# lightbar_control.net
KiCad netlist of a schematic drawn in EAGLE
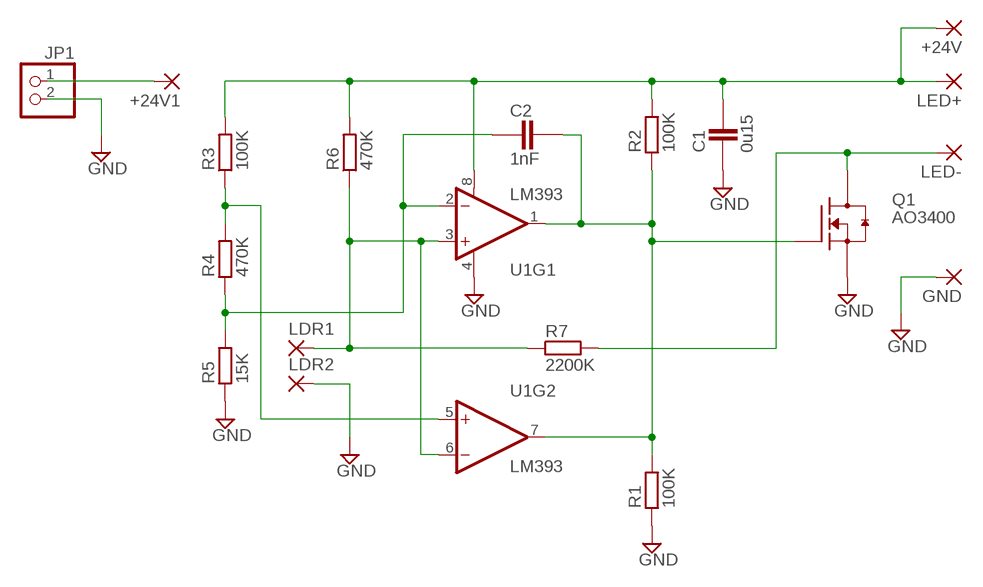
[diagram p0: schematic, sheet 1]

(export (version "E")
  (design (tool "Eeschema 10.0.6"))
  (components
    (comp (ref "+24V")
      (value "SMD2")
      (footprint "eagle-import:SMD1,27-2,54")
      (libsource (lib "eagle-import") (part "SMD2"))
    )
    (comp (ref "+24V1")
      (value "SMD2")
      (footprint "eagle-import:SMD1,27-2,54")
      (libsource (lib "eagle-import") (part "SMD2"))
    )
    (comp (ref "C1")
      (value "0u15")
      (footprint "eagle-import:CAPC2012X145AN")
      (libsource (lib "eagle-import") (part "CAPACITOR_0805"))
    )
    (comp (ref "C2")
      (value "1nF")
      (footprint "eagle-import:CAPC1608X92N")
      (libsource (lib "eagle-import") (part "CAPACITOR_0603"))
    )
    (comp (ref "GND")
      (value "SMD2")
      (footprint "eagle-import:SMD1,27-2,54")
      (libsource (lib "eagle-import") (part "SMD2"))
    )
    (comp (ref "JP1")
      (value "PINHD-1X2/90")
      (footprint "eagle-import:1X02_90")
      (libsource (lib "eagle-import") (part "PINHD-1X2/90"))
    )
    (comp (ref "LDR1")
      (value "SMD2")
      (footprint "eagle-import:SMD1,27-2,54")
      (libsource (lib "eagle-import") (part "SMD2"))
    )
    (comp (ref "LDR2")
      (value "SMD2")
      (footprint "eagle-import:SMD1,27-2,54")
      (libsource (lib "eagle-import") (part "SMD2"))
    )
    (comp (ref "LED+")
      (value "SMD2")
      (footprint "eagle-import:SMD1,27-2,54")
      (libsource (lib "eagle-import") (part "SMD2"))
    )
    (comp (ref "LED-")
      (value "SMD2")
      (footprint "eagle-import:SMD1,27-2,54")
      (libsource (lib "eagle-import") (part "SMD2"))
    )
    (comp (ref "Q1")
      (value "AO3400")
      (footprint "eagle-import:SOT95P280X135-3N")
      (libsource (lib "eagle-import") (part "MOSFET-NCH_SOT-23"))
    )
    (comp (ref "R1")
      (value "100K")
      (footprint "eagle-import:RESC1608X55N")
      (libsource (lib "eagle-import") (part "RESISTOR_0603"))
    )
    (comp (ref "R2")
      (value "100K")
      (footprint "eagle-import:RESC1608X55N")
      (libsource (lib "eagle-import") (part "RESISTOR_0603"))
    )
    (comp (ref "R3")
      (value "100K")
      (footprint "eagle-import:RESC1608X55N")
      (libsource (lib "eagle-import") (part "RESISTOR_0603"))
    )
    (comp (ref "R4")
      (value "470K")
      (footprint "eagle-import:RESC1608X55N")
      (libsource (lib "eagle-import") (part "RESISTOR_0603"))
    )
    (comp (ref "R5")
      (value "15K")
      (footprint "eagle-import:RESC1608X55N")
      (libsource (lib "eagle-import") (part "RESISTOR_0603"))
    )
    (comp (ref "R6")
      (value "470K")
      (footprint "eagle-import:RESC1608X55N")
      (libsource (lib "eagle-import") (part "RESISTOR_0603"))
    )
    (comp (ref "R7")
      (value "2200K")
      (footprint "eagle-import:RESC2012X70N")
      (libsource (lib "eagle-import") (part "RESISTOR_0805"))
    )
    (comp (ref "U1")
      (value "LM393")
      (footprint "eagle-import:SO08")
      (libsource (lib "eagle-import") (part "LM393"))
    )
  )
  (nets
    (net (code "1") (name "GND") (class "Default")
      (node (ref "C1") (pin "1") (pinfunction "1_1") (pintype "passive"))
      (node (ref "GND") (pin "1") (pinfunction "P_1") (pintype "passive"))
      (node (ref "JP1") (pin "2") (pinfunction "2_2") (pintype "passive"))
      (node (ref "LDR2") (pin "1") (pinfunction "P_1") (pintype "passive"))
      (node (ref "Q1") (pin "2") (pinfunction "S_2") (pintype "passive"))
      (node (ref "R1") (pin "1") (pinfunction "1_1") (pintype "passive"))
      (node (ref "R5") (pin "1") (pinfunction "1_1") (pintype "passive"))
      (node (ref "U1") (pin "4") (pinfunction "V-_4") (pintype "power_in"))
    )
    (net (code "2") (name "Net-(+24V-P)") (class "Default")
      (node (ref "+24V") (pin "1") (pinfunction "P_1") (pintype "passive"))
      (node (ref "C1") (pin "2") (pinfunction "2_2") (pintype "passive"))
      (node (ref "LED+") (pin "1") (pinfunction "P_1") (pintype "passive"))
      (node (ref "R2") (pin "2") (pinfunction "2_2") (pintype "passive"))
      (node (ref "R3") (pin "2") (pinfunction "2_2") (pintype "passive"))
      (node (ref "R6") (pin "2") (pinfunction "2_2") (pintype "passive"))
      (node (ref "U1") (pin "8") (pinfunction "V+_8") (pintype "power_in"))
    )
    (net (code "3") (name "Net-(+24V1-P)") (class "Default")
      (node (ref "+24V1") (pin "1") (pinfunction "P_1") (pintype "passive"))
      (node (ref "JP1") (pin "1") (pinfunction "1_1") (pintype "passive"))
    )
    (net (code "4") (name "Net-(LDR1-P)") (class "Default")
      (node (ref "LDR1") (pin "1") (pinfunction "P_1") (pintype "passive"))
      (node (ref "R6") (pin "1") (pinfunction "1_1") (pintype "passive"))
      (node (ref "R7") (pin "1") (pinfunction "1_1") (pintype "passive"))
      (node (ref "U1") (pin "3") (pinfunction "+IN_3") (pintype "input"))
      (node (ref "U1") (pin "6") (pinfunction "-IN_6") (pintype "input"))
    )
    (net (code "5") (name "Net-(LED--P)") (class "Default")
      (node (ref "LED-") (pin "1") (pinfunction "P_1") (pintype "passive"))
      (node (ref "Q1") (pin "3") (pinfunction "D_3") (pintype "passive"))
      (node (ref "R7") (pin "2") (pinfunction "2_2") (pintype "passive"))
    )
    (net (code "6") (name "Net-(Q1-G)") (class "Default")
      (node (ref "C2") (pin "2") (pinfunction "2_2") (pintype "passive"))
      (node (ref "Q1") (pin "1") (pinfunction "G_1") (pintype "passive"))
      (node (ref "R1") (pin "2") (pinfunction "2_2") (pintype "passive"))
      (node (ref "R2") (pin "1") (pinfunction "1_1") (pintype "passive"))
      (node (ref "U1") (pin "1") (pinfunction "OUT_1") (pintype "output"))
      (node (ref "U1") (pin "7") (pinfunction "OUT_7") (pintype "output"))
    )
    (net (code "7") (name "Net-(U1A--IN)") (class "Default")
      (node (ref "C2") (pin "1") (pinfunction "1_1") (pintype "passive"))
      (node (ref "R4") (pin "1") (pinfunction "1_1") (pintype "passive"))
      (node (ref "R5") (pin "2") (pinfunction "2_2") (pintype "passive"))
      (node (ref "U1") (pin "2") (pinfunction "-IN_2") (pintype "input"))
    )
    (net (code "8") (name "Net-(U1B-+IN)") (class "Default")
      (node (ref "R3") (pin "1") (pinfunction "1_1") (pintype "passive"))
      (node (ref "R4") (pin "2") (pinfunction "2_2") (pintype "passive"))
      (node (ref "U1") (pin "5") (pinfunction "+IN_5") (pintype "input"))
    )
  )
)
